# lightctrl.net
KiCad netlist of a schematic drawn in EAGLE
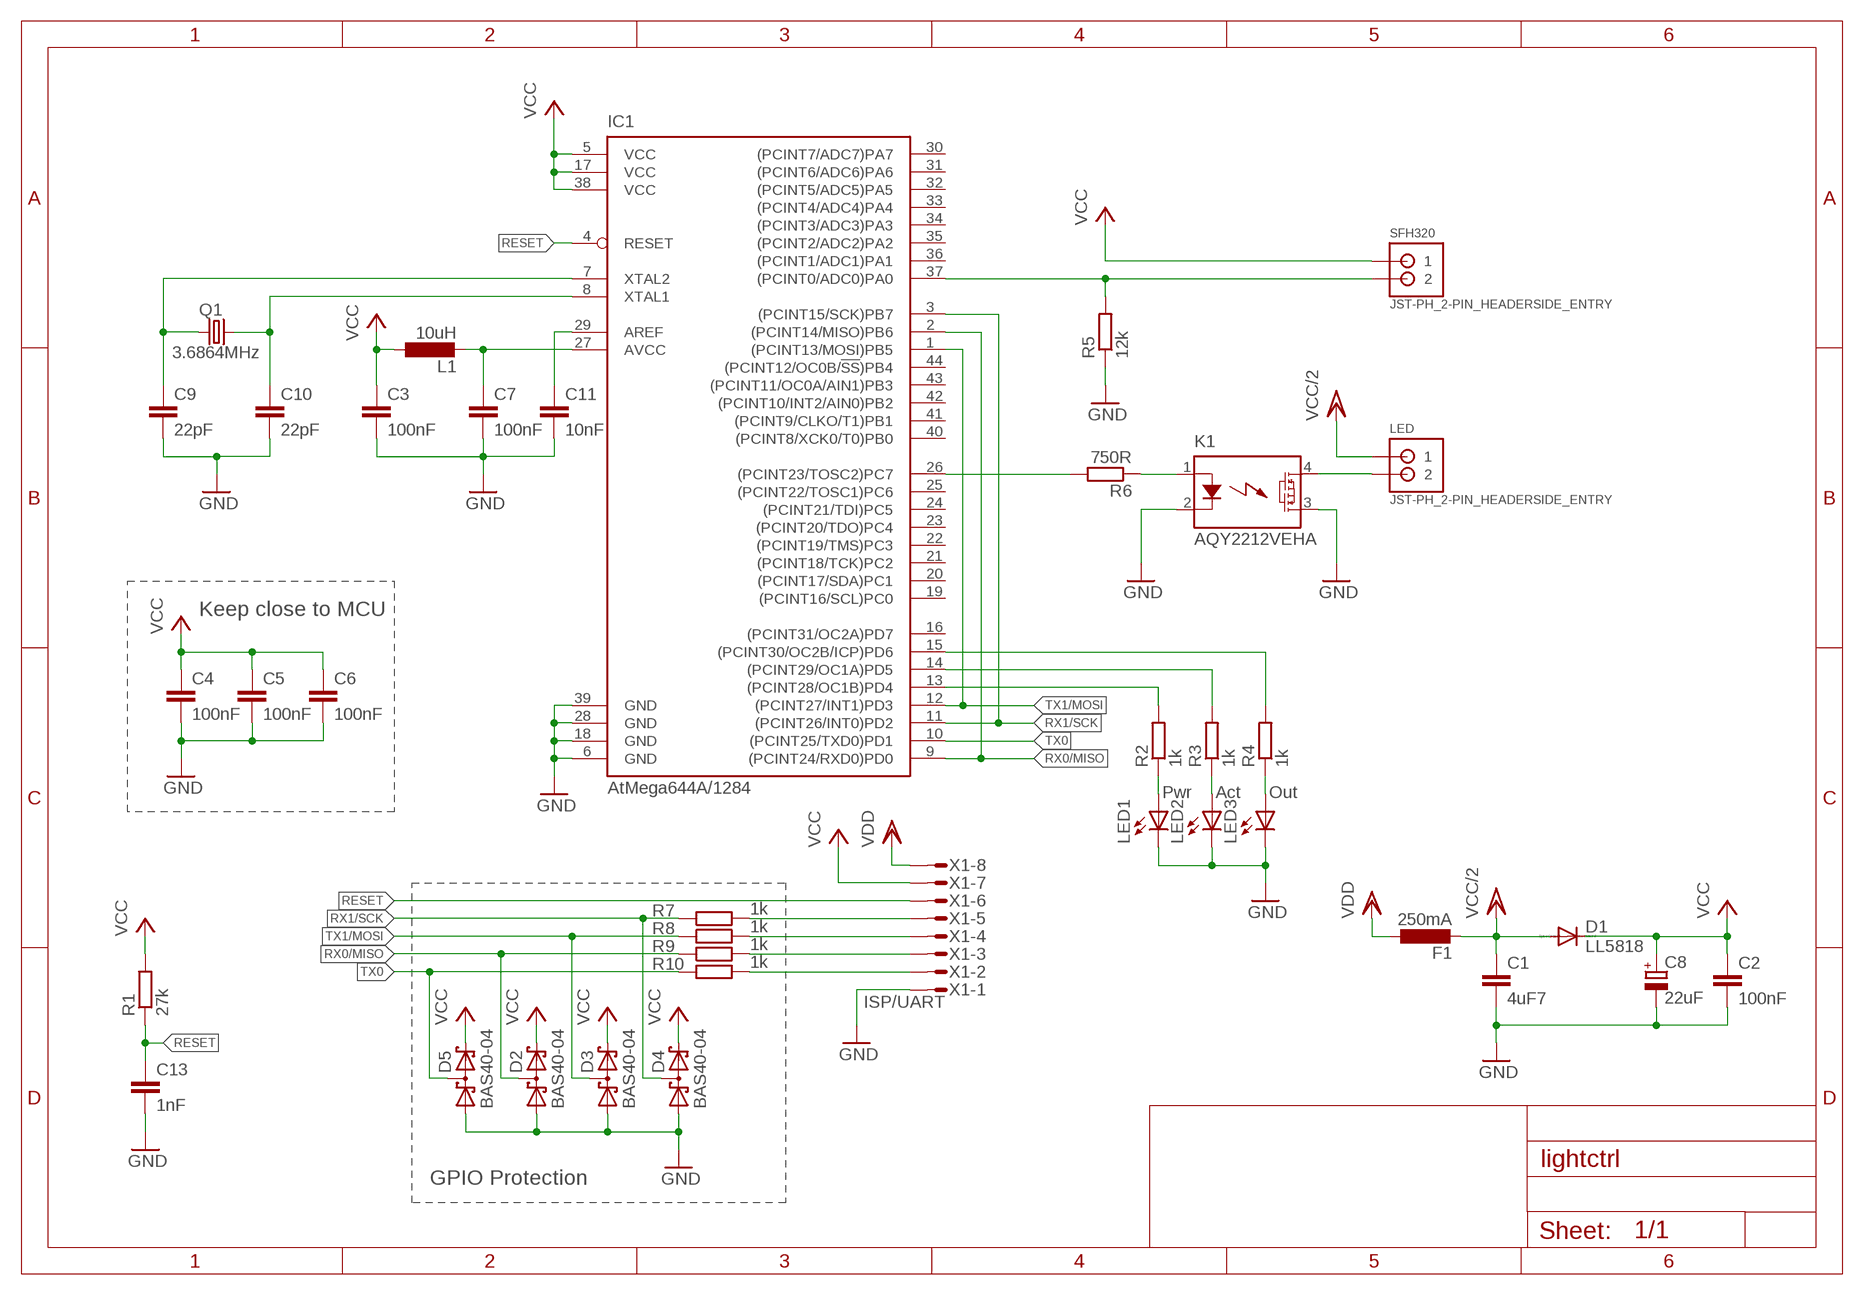
[diagram p0: schematic, sheet 1]

(export (version "E")
  (design (tool "Eeschema 10.0.6"))
  (components
    (comp (ref "C1")
      (value "4uF7")
      (footprint "eagle-import:C1206")
      (libsource (lib "eagle-import") (part "C-EUC1206"))
    )
    (comp (ref "C2")
      (value "100nF")
      (footprint "eagle-import:C1206")
      (libsource (lib "eagle-import") (part "C-EUC1206"))
    )
    (comp (ref "C3")
      (value "100nF")
      (footprint "eagle-import:C1206")
      (libsource (lib "eagle-import") (part "C-EUC1206"))
    )
    (comp (ref "C4")
      (value "100nF")
      (footprint "eagle-import:C1206")
      (libsource (lib "eagle-import") (part "C-EUC1206"))
    )
    (comp (ref "C5")
      (value "100nF")
      (footprint "eagle-import:C1206")
      (libsource (lib "eagle-import") (part "C-EUC1206"))
    )
    (comp (ref "C6")
      (value "100nF")
      (footprint "eagle-import:C1206")
      (libsource (lib "eagle-import") (part "C-EUC1206"))
    )
    (comp (ref "C7")
      (value "100nF")
      (footprint "eagle-import:C1206")
      (libsource (lib "eagle-import") (part "C-EUC1206"))
    )
    (comp (ref "C8")
      (value "22uF")
      (footprint "eagle-import:SMC_D")
      (libsource (lib "eagle-import") (part "CPOL-EUSMCD"))
    )
    (comp (ref "C9")
      (value "22pF")
      (footprint "eagle-import:C1206")
      (libsource (lib "eagle-import") (part "C-EUC1206"))
    )
    (comp (ref "C10")
      (value "22pF")
      (footprint "eagle-import:C1206")
      (libsource (lib "eagle-import") (part "C-EUC1206"))
    )
    (comp (ref "C11")
      (value "10nF")
      (footprint "eagle-import:C1206")
      (libsource (lib "eagle-import") (part "C-EUC1206"))
    )
    (comp (ref "C13")
      (value "1nF")
      (footprint "eagle-import:C1206")
      (libsource (lib "eagle-import") (part "C-EUC1206"))
    )
    (comp (ref "D1")
      (value "LL5818")
      (footprint "eagle-import:MELF-MLL41")
      (libsource (lib "eagle-import") (part "DIODE-MELF-MLL41"))
    )
    (comp (ref "D2")
      (value "BAS40-04")
      (footprint "eagle-import:SOT23")
      (libsource (lib "eagle-import") (part "BAS40-04"))
    )
    (comp (ref "D3")
      (value "BAS40-04")
      (footprint "eagle-import:SOT23")
      (libsource (lib "eagle-import") (part "BAS40-04"))
    )
    (comp (ref "D4")
      (value "BAS40-04")
      (footprint "eagle-import:SOT23")
      (libsource (lib "eagle-import") (part "BAS40-04"))
    )
    (comp (ref "D5")
      (value "BAS40-04")
      (footprint "eagle-import:SOT23")
      (libsource (lib "eagle-import") (part "BAS40-04"))
    )
    (comp (ref "F1")
      (value "250mA")
      (footprint "eagle-import:L1812")
      (libsource (lib "eagle-import") (part "L-EUL1812"))
    )
    (comp (ref "IC1")
      (value "AtMega644A/1284")
      (footprint "eagle-import:TQFP44")
      (fields (field (name "MPN") "ATMEGA644PV-10AU"))
      (libsource (lib "eagle-import") (part "ATMEGA644A"))
    )
    (comp (ref "K1")
      (value "AQY2212VEHA")
      (footprint "eagle-import:SMD-DIP04")
      (libsource (lib "eagle-import") (part "AQY2212VEHA"))
    )
    (comp (ref "L1")
      (value "10uH")
      (footprint "eagle-import:L3230M")
      (libsource (lib "eagle-import") (part "L-EUL3230M"))
    )
    (comp (ref "LED")
      (value "JST-PH_2-PIN_HEADERSIDE_ENTRY")
      (footprint "eagle-import:S2B-PH_HEADER")
      (libsource (lib "eagle-import") (part "JST-PH_2-PIN_HEADERSIDE_ENTRY"))
    )
    (comp (ref "LED1")
      (value "Pwr")
      (footprint "eagle-import:CHIPLED_1206")
      (libsource (lib "eagle-import") (part "LEDCHIPLED_1206"))
    )
    (comp (ref "LED2")
      (value "Act")
      (footprint "eagle-import:CHIPLED_1206")
      (libsource (lib "eagle-import") (part "LEDCHIPLED_1206"))
    )
    (comp (ref "LED3")
      (value "Out")
      (footprint "eagle-import:CHIPLED_1206")
      (libsource (lib "eagle-import") (part "LEDCHIPLED_1206"))
    )
    (comp (ref "Q1")
      (value "3.6864MHz")
      (footprint "eagle-import:HC49UP")
      (libsource (lib "eagle-import") (part "CRYSTALHC49UP"))
    )
    (comp (ref "R1")
      (value "27k")
      (footprint "eagle-import:R1206")
      (libsource (lib "eagle-import") (part "R-EU_R1206"))
    )
    (comp (ref "R2")
      (value "1k")
      (footprint "eagle-import:R1206")
      (libsource (lib "eagle-import") (part "R-EU_R1206"))
    )
    (comp (ref "R3")
      (value "1k")
      (footprint "eagle-import:R1206")
      (libsource (lib "eagle-import") (part "R-EU_R1206"))
    )
    (comp (ref "R4")
      (value "1k")
      (footprint "eagle-import:R1206")
      (libsource (lib "eagle-import") (part "R-EU_R1206"))
    )
    (comp (ref "R5")
      (value "12k")
      (footprint "eagle-import:R1206")
      (libsource (lib "eagle-import") (part "R-EU_R1206"))
    )
    (comp (ref "R6")
      (value "750R")
      (footprint "eagle-import:R1206")
      (libsource (lib "eagle-import") (part "R-EU_R1206"))
    )
    (comp (ref "R7")
      (value "1k")
      (footprint "eagle-import:R1206")
      (libsource (lib "eagle-import") (part "R-EU_R1206"))
    )
    (comp (ref "R8")
      (value "1k")
      (footprint "eagle-import:R1206")
      (libsource (lib "eagle-import") (part "R-EU_R1206"))
    )
    (comp (ref "R9")
      (value "1k")
      (footprint "eagle-import:R1206")
      (libsource (lib "eagle-import") (part "R-EU_R1206"))
    )
    (comp (ref "R10")
      (value "1k")
      (footprint "eagle-import:R1206")
      (libsource (lib "eagle-import") (part "R-EU_R1206"))
    )
    (comp (ref "SFH320")
      (value "JST-PH_2-PIN_HEADERSIDE_ENTRY")
      (footprint "eagle-import:S2B-PH_HEADER")
      (libsource (lib "eagle-import") (part "JST-PH_2-PIN_HEADERSIDE_ENTRY"))
    )
    (comp (ref "X1")
      (value "ISP/UART")
      (footprint "eagle-import:MICROMATCH-8")
      (fields (field (name "MF") "FARNELL") (field (name "MPN") "7-215464-8"))
      (libsource (lib "eagle-import") (part "MICROMATCH-8"))
    )
  )
  (nets
    (net (code "1") (name "GND") (class "Default")
      (node (ref "C1") (pin "2") (pinfunction "2_2") (pintype "passive"))
      (node (ref "C10") (pin "2") (pinfunction "2_2") (pintype "passive"))
      (node (ref "C11") (pin "2") (pinfunction "2_2") (pintype "passive"))
      (node (ref "C13") (pin "2") (pinfunction "2_2") (pintype "passive"))
      (node (ref "C2") (pin "2") (pinfunction "2_2") (pintype "passive"))
      (node (ref "C3") (pin "2") (pinfunction "2_2") (pintype "passive"))
      (node (ref "C4") (pin "2") (pinfunction "2_2") (pintype "passive"))
      (node (ref "C5") (pin "2") (pinfunction "2_2") (pintype "passive"))
      (node (ref "C6") (pin "2") (pinfunction "2_2") (pintype "passive"))
      (node (ref "C7") (pin "2") (pinfunction "2_2") (pintype "passive"))
      (node (ref "C8") (pin "-") (pinfunction "-_-") (pintype "passive"))
      (node (ref "C9") (pin "2") (pinfunction "2_2") (pintype "passive"))
      (node (ref "D2") (pin "1") (pinfunction "A1_1") (pintype "passive"))
      (node (ref "D3") (pin "1") (pinfunction "A1_1") (pintype "passive"))
      (node (ref "D4") (pin "1") (pinfunction "A1_1") (pintype "passive"))
      (node (ref "D5") (pin "1") (pinfunction "A1_1") (pintype "passive"))
      (node (ref "IC1") (pin "18") (pinfunction "GND_18") (pintype "power_in"))
      (node (ref "IC1") (pin "28") (pinfunction "GND_28") (pintype "power_in"))
      (node (ref "IC1") (pin "39") (pinfunction "GND_39") (pintype "power_in"))
      (node (ref "IC1") (pin "6") (pinfunction "GND_6") (pintype "power_in"))
      (node (ref "K1") (pin "2") (pinfunction "K_2") (pintype "passive"))
      (node (ref "K1") (pin "3") (pinfunction "DS2_3") (pintype "passive"))
      (node (ref "LED1") (pin "C") (pinfunction "C_C") (pintype "passive"))
      (node (ref "LED2") (pin "C") (pinfunction "C_C") (pintype "passive"))
      (node (ref "LED3") (pin "C") (pinfunction "C_C") (pintype "passive"))
      (node (ref "R5") (pin "1") (pinfunction "1_1") (pintype "passive"))
      (node (ref "X1") (pin "1") (pinfunction "S_1") (pintype "passive"))
    )
    (net (code "2") (name "Net-(IC1-(PCINT0{slash}ADC0)PA0)") (class "Default")
      (node (ref "IC1") (pin "37") (pinfunction "(PCINT0/ADC0)PA0_37") (pintype "bidirectional"))
      (node (ref "R5") (pin "2") (pinfunction "2_2") (pintype "passive"))
      (node (ref "SFH320") (pin "P2") (pinfunction "2_P2") (pintype "bidirectional"))
    )
    (net (code "3") (name "Net-(IC1-(PCINT23{slash}TOSC2)PC7)") (class "Default")
      (node (ref "IC1") (pin "26") (pinfunction "(PCINT23/TOSC2)PC7_26") (pintype "output"))
      (node (ref "R6") (pin "2") (pinfunction "2_2") (pintype "passive"))
    )
    (net (code "4") (name "Net-(IC1-(PCINT28{slash}OC1B)PD4)") (class "Default")
      (node (ref "IC1") (pin "13") (pinfunction "(PCINT28/OC1B)PD4_13") (pintype "bidirectional"))
      (node (ref "R2") (pin "2") (pinfunction "2_2") (pintype "passive"))
    )
    (net (code "5") (name "Net-(IC1-(PCINT29{slash}OC1A)PD5)") (class "Default")
      (node (ref "IC1") (pin "14") (pinfunction "(PCINT29/OC1A)PD5_14") (pintype "bidirectional"))
      (node (ref "R3") (pin "2") (pinfunction "2_2") (pintype "passive"))
    )
    (net (code "6") (name "Net-(IC1-(PCINT30{slash}OC2B{slash}ICP)PD6)") (class "Default")
      (node (ref "IC1") (pin "15") (pinfunction "(PCINT30/OC2B/ICP)PD6_15") (pintype "bidirectional"))
      (node (ref "R4") (pin "2") (pinfunction "2_2") (pintype "passive"))
    )
    (net (code "7") (name "Net-(IC1-AREF)") (class "Default")
      (node (ref "C11") (pin "1") (pinfunction "1_1") (pintype "passive"))
      (node (ref "IC1") (pin "29") (pinfunction "AREF_29") (pintype "passive"))
    )
    (net (code "8") (name "Net-(IC1-AVCC)") (class "Default")
      (node (ref "C7") (pin "1") (pinfunction "1_1") (pintype "passive"))
      (node (ref "IC1") (pin "27") (pinfunction "AVCC_27") (pintype "power_in"))
      (node (ref "L1") (pin "2") (pinfunction "2_2") (pintype "passive"))
    )
    (net (code "9") (name "Net-(IC1-XTAL1)") (class "Default")
      (node (ref "C10") (pin "1") (pinfunction "1_1") (pintype "passive"))
      (node (ref "IC1") (pin "8") (pinfunction "XTAL1_8") (pintype "bidirectional"))
      (node (ref "Q1") (pin "2") (pinfunction "2_2") (pintype "passive"))
    )
    (net (code "10") (name "Net-(IC1-XTAL2)") (class "Default")
      (node (ref "C9") (pin "1") (pinfunction "1_1") (pintype "passive"))
      (node (ref "IC1") (pin "7") (pinfunction "XTAL2_7") (pintype "bidirectional"))
      (node (ref "Q1") (pin "1") (pinfunction "1_1") (pintype "passive"))
    )
    (net (code "11") (name "Net-(K1-A)") (class "Default")
      (node (ref "K1") (pin "1") (pinfunction "A_1") (pintype "passive"))
      (node (ref "R6") (pin "1") (pinfunction "1_1") (pintype "passive"))
    )
    (net (code "12") (name "Net-(K1-DS1)") (class "Default")
      (node (ref "K1") (pin "4") (pinfunction "DS1_4") (pintype "passive"))
      (node (ref "LED") (pin "P2") (pinfunction "2_P2") (pintype "bidirectional"))
    )
    (net (code "13") (name "Net-(LED1-PadA)") (class "Default")
      (node (ref "LED1") (pin "A") (pinfunction "A_A") (pintype "passive"))
      (node (ref "R2") (pin "1") (pinfunction "1_1") (pintype "passive"))
    )
    (net (code "14") (name "Net-(LED2-PadA)") (class "Default")
      (node (ref "LED2") (pin "A") (pinfunction "A_A") (pintype "passive"))
      (node (ref "R3") (pin "1") (pinfunction "1_1") (pintype "passive"))
    )
    (net (code "15") (name "Net-(LED3-PadA)") (class "Default")
      (node (ref "LED3") (pin "A") (pinfunction "A_A") (pintype "passive"))
      (node (ref "R4") (pin "1") (pinfunction "1_1") (pintype "passive"))
    )
    (net (code "16") (name "Net-(X1B-S)") (class "Default")
      (node (ref "R10") (pin "2") (pinfunction "2_2") (pintype "passive"))
      (node (ref "X1") (pin "2") (pinfunction "S_2") (pintype "passive"))
    )
    (net (code "17") (name "Net-(X1C-S)") (class "Default")
      (node (ref "R9") (pin "2") (pinfunction "2_2") (pintype "passive"))
      (node (ref "X1") (pin "3") (pinfunction "S_3") (pintype "passive"))
    )
    (net (code "18") (name "Net-(X1D-S)") (class "Default")
      (node (ref "R8") (pin "2") (pinfunction "2_2") (pintype "passive"))
      (node (ref "X1") (pin "4") (pinfunction "S_4") (pintype "passive"))
    )
    (net (code "19") (name "Net-(X1E-S)") (class "Default")
      (node (ref "R7") (pin "2") (pinfunction "2_2") (pintype "passive"))
      (node (ref "X1") (pin "5") (pinfunction "S_5") (pintype "passive"))
    )
    (net (code "20") (name "RESET") (class "Default")
      (node (ref "C13") (pin "1") (pinfunction "1_1") (pintype "passive"))
      (node (ref "IC1") (pin "4") (pinfunction "RESET_4") (pintype "input"))
      (node (ref "R1") (pin "1") (pinfunction "1_1") (pintype "passive"))
      (node (ref "X1") (pin "6") (pinfunction "S_6") (pintype "passive"))
    )
    (net (code "21") (name "RX0{slash}MISO") (class "Default")
      (node (ref "D2") (pin "3") (pinfunction "C1A2_3") (pintype "passive"))
      (node (ref "IC1") (pin "2") (pinfunction "(PCINT14/MISO)PB6_2") (pintype "bidirectional"))
      (node (ref "IC1") (pin "9") (pinfunction "(PCINT24/RXD0)PD0_9") (pintype "bidirectional"))
      (node (ref "R9") (pin "1") (pinfunction "1_1") (pintype "passive"))
    )
    (net (code "22") (name "RX1{slash}SCK") (class "Default")
      (node (ref "D4") (pin "3") (pinfunction "C1A2_3") (pintype "passive"))
      (node (ref "IC1") (pin "11") (pinfunction "(PCINT26/INT0)PD2_11") (pintype "bidirectional"))
      (node (ref "IC1") (pin "3") (pinfunction "(PCINT15/SCK)PB7_3") (pintype "bidirectional"))
      (node (ref "R7") (pin "1") (pinfunction "1_1") (pintype "passive"))
    )
    (net (code "23") (name "TX0") (class "Default")
      (node (ref "D5") (pin "3") (pinfunction "C1A2_3") (pintype "passive"))
      (node (ref "IC1") (pin "10") (pinfunction "(PCINT25/TXD0)PD1_10") (pintype "bidirectional"))
      (node (ref "R10") (pin "1") (pinfunction "1_1") (pintype "passive"))
    )
    (net (code "24") (name "TX1{slash}MOSI") (class "Default")
      (node (ref "D3") (pin "3") (pinfunction "C1A2_3") (pintype "passive"))
      (node (ref "IC1") (pin "1") (pinfunction "(PCINT13/MOSI)PB5_1") (pintype "bidirectional"))
      (node (ref "IC1") (pin "12") (pinfunction "(PCINT27/INT1)PD3_12") (pintype "bidirectional"))
      (node (ref "R8") (pin "1") (pinfunction "1_1") (pintype "passive"))
    )
    (net (code "25") (name "VCC") (class "Default")
      (node (ref "C2") (pin "1") (pinfunction "1_1") (pintype "passive"))
      (node (ref "C3") (pin "1") (pinfunction "1_1") (pintype "passive"))
      (node (ref "C4") (pin "1") (pinfunction "1_1") (pintype "passive"))
      (node (ref "C5") (pin "1") (pinfunction "1_1") (pintype "passive"))
      (node (ref "C6") (pin "1") (pinfunction "1_1") (pintype "passive"))
      (node (ref "C8") (pin "+") (pinfunction "+_+") (pintype "passive"))
      (node (ref "D1") (pin "C") (pinfunction "C_C") (pintype "passive"))
      (node (ref "D2") (pin "2") (pinfunction "C2_2") (pintype "passive"))
      (node (ref "D3") (pin "2") (pinfunction "C2_2") (pintype "passive"))
      (node (ref "D4") (pin "2") (pinfunction "C2_2") (pintype "passive"))
      (node (ref "D5") (pin "2") (pinfunction "C2_2") (pintype "passive"))
      (node (ref "IC1") (pin "17") (pinfunction "VCC_17") (pintype "power_in"))
      (node (ref "IC1") (pin "38") (pinfunction "VCC_38") (pintype "power_in"))
      (node (ref "IC1") (pin "5") (pinfunction "VCC_5") (pintype "power_in"))
      (node (ref "L1") (pin "1") (pinfunction "1_1") (pintype "passive"))
      (node (ref "R1") (pin "2") (pinfunction "2_2") (pintype "passive"))
      (node (ref "SFH320") (pin "P1") (pinfunction "1_P1") (pintype "bidirectional"))
      (node (ref "X1") (pin "7") (pinfunction "S_7") (pintype "passive"))
    )
    (net (code "26") (name "VCC{slash}2") (class "Default")
      (node (ref "C1") (pin "1") (pinfunction "1_1") (pintype "passive"))
      (node (ref "D1") (pin "A") (pinfunction "A_A") (pintype "passive"))
      (node (ref "F1") (pin "2") (pinfunction "2_2") (pintype "passive"))
      (node (ref "LED") (pin "P1") (pinfunction "1_P1") (pintype "bidirectional"))
    )
    (net (code "27") (name "VDD") (class "Default")
      (node (ref "F1") (pin "1") (pinfunction "1_1") (pintype "passive"))
      (node (ref "X1") (pin "8") (pinfunction "S_8") (pintype "passive"))
    )
    (net (code "28") (name "unconnected-(IC1-(PCINT1{slash}ADC1)PA1-Pad36)") (class "Default")
      (node (ref "IC1") (pin "36") (pinfunction "(PCINT1/ADC1)PA1_36") (pintype "bidirectional"))
    )
    (net (code "29") (name "unconnected-(IC1-(PCINT2{slash}ADC2)PA2-Pad35)") (class "Default")
      (node (ref "IC1") (pin "35") (pinfunction "(PCINT2/ADC2)PA2_35") (pintype "bidirectional"))
    )
    (net (code "30") (name "unconnected-(IC1-(PCINT3{slash}ADC3)PA3-Pad34)") (class "Default")
      (node (ref "IC1") (pin "34") (pinfunction "(PCINT3/ADC3)PA3_34") (pintype "bidirectional"))
    )
    (net (code "31") (name "unconnected-(IC1-(PCINT4{slash}ADC4)PA4-Pad33)") (class "Default")
      (node (ref "IC1") (pin "33") (pinfunction "(PCINT4/ADC4)PA4_33") (pintype "bidirectional"))
    )
    (net (code "32") (name "unconnected-(IC1-(PCINT5{slash}ADC5)PA5-Pad32)") (class "Default")
      (node (ref "IC1") (pin "32") (pinfunction "(PCINT5/ADC5)PA5_32") (pintype "bidirectional"))
    )
    (net (code "33") (name "unconnected-(IC1-(PCINT6{slash}ADC6)PA6-Pad31)") (class "Default")
      (node (ref "IC1") (pin "31") (pinfunction "(PCINT6/ADC6)PA6_31") (pintype "bidirectional"))
    )
    (net (code "34") (name "unconnected-(IC1-(PCINT7{slash}ADC7)PA7-Pad30)") (class "Default")
      (node (ref "IC1") (pin "30") (pinfunction "(PCINT7/ADC7)PA7_30") (pintype "bidirectional"))
    )
    (net (code "35") (name "unconnected-(IC1-(PCINT8{slash}XCK0{slash}T0)PB0-Pad40)") (class "Default")
      (node (ref "IC1") (pin "40") (pinfunction "(PCINT8/XCK0/T0)PB0_40") (pintype "bidirectional"))
    )
    (net (code "36") (name "unconnected-(IC1-(PCINT9{slash}CLKO{slash}T1)PB1-Pad41)") (class "Default")
      (node (ref "IC1") (pin "41") (pinfunction "(PCINT9/CLKO/T1)PB1_41") (pintype "bidirectional"))
    )
    (net (code "37") (name "unconnected-(IC1-(PCINT10{slash}INT2{slash}AIN0)PB2-Pad42)") (class "Default")
      (node (ref "IC1") (pin "42") (pinfunction "(PCINT10/INT2/AIN0)PB2_42") (pintype "bidirectional"))
    )
    (net (code "38") (name "unconnected-(IC1-(PCINT11{slash}OC0A{slash}AIN1)PB3-Pad43)") (class "Default")
      (node (ref "IC1") (pin "43") (pinfunction "(PCINT11/OC0A/AIN1)PB3_43") (pintype "bidirectional"))
    )
    (net (code "39") (name "unconnected-(IC1-(PCINT12{slash}OC0B{slash}~{SS})PB4-Pad44)") (class "Default")
      (node (ref "IC1") (pin "44") (pinfunction "(PCINT12/OC0B/~{SS})PB4_44") (pintype "bidirectional"))
    )
    (net (code "40") (name "unconnected-(IC1-(PCINT16{slash}SCL)PC0-Pad19)") (class "Default")
      (node (ref "IC1") (pin "19") (pinfunction "(PCINT16/SCL)PC0_19") (pintype "output"))
    )
    (net (code "41") (name "unconnected-(IC1-(PCINT17{slash}SDA)PC1-Pad20)") (class "Default")
      (node (ref "IC1") (pin "20") (pinfunction "(PCINT17/SDA)PC1_20") (pintype "output"))
    )
    (net (code "42") (name "unconnected-(IC1-(PCINT18{slash}TCK)PC2-Pad21)") (class "Default")
      (node (ref "IC1") (pin "21") (pinfunction "(PCINT18/TCK)PC2_21") (pintype "output"))
    )
    (net (code "43") (name "unconnected-(IC1-(PCINT19{slash}TMS)PC3-Pad22)") (class "Default")
      (node (ref "IC1") (pin "22") (pinfunction "(PCINT19/TMS)PC3_22") (pintype "output"))
    )
    (net (code "44") (name "unconnected-(IC1-(PCINT20{slash}TDO)PC4-Pad23)") (class "Default")
      (node (ref "IC1") (pin "23") (pinfunction "(PCINT20/TDO)PC4_23") (pintype "output"))
    )
    (net (code "45") (name "unconnected-(IC1-(PCINT21{slash}TDI)PC5-Pad24)") (class "Default")
      (node (ref "IC1") (pin "24") (pinfunction "(PCINT21/TDI)PC5_24") (pintype "output"))
    )
    (net (code "46") (name "unconnected-(IC1-(PCINT22{slash}TOSC1)PC6-Pad25)") (class "Default")
      (node (ref "IC1") (pin "25") (pinfunction "(PCINT22/TOSC1)PC6_25") (pintype "output"))
    )
    (net (code "47") (name "unconnected-(IC1-(PCINT31{slash}OC2A)PD7-Pad16)") (class "Default")
      (node (ref "IC1") (pin "16") (pinfunction "(PCINT31/OC2A)PD7_16") (pintype "bidirectional"))
    )
  )
)
